# Qwiic_Scale.net
KiCad netlist of a schematic drawn in EAGLE
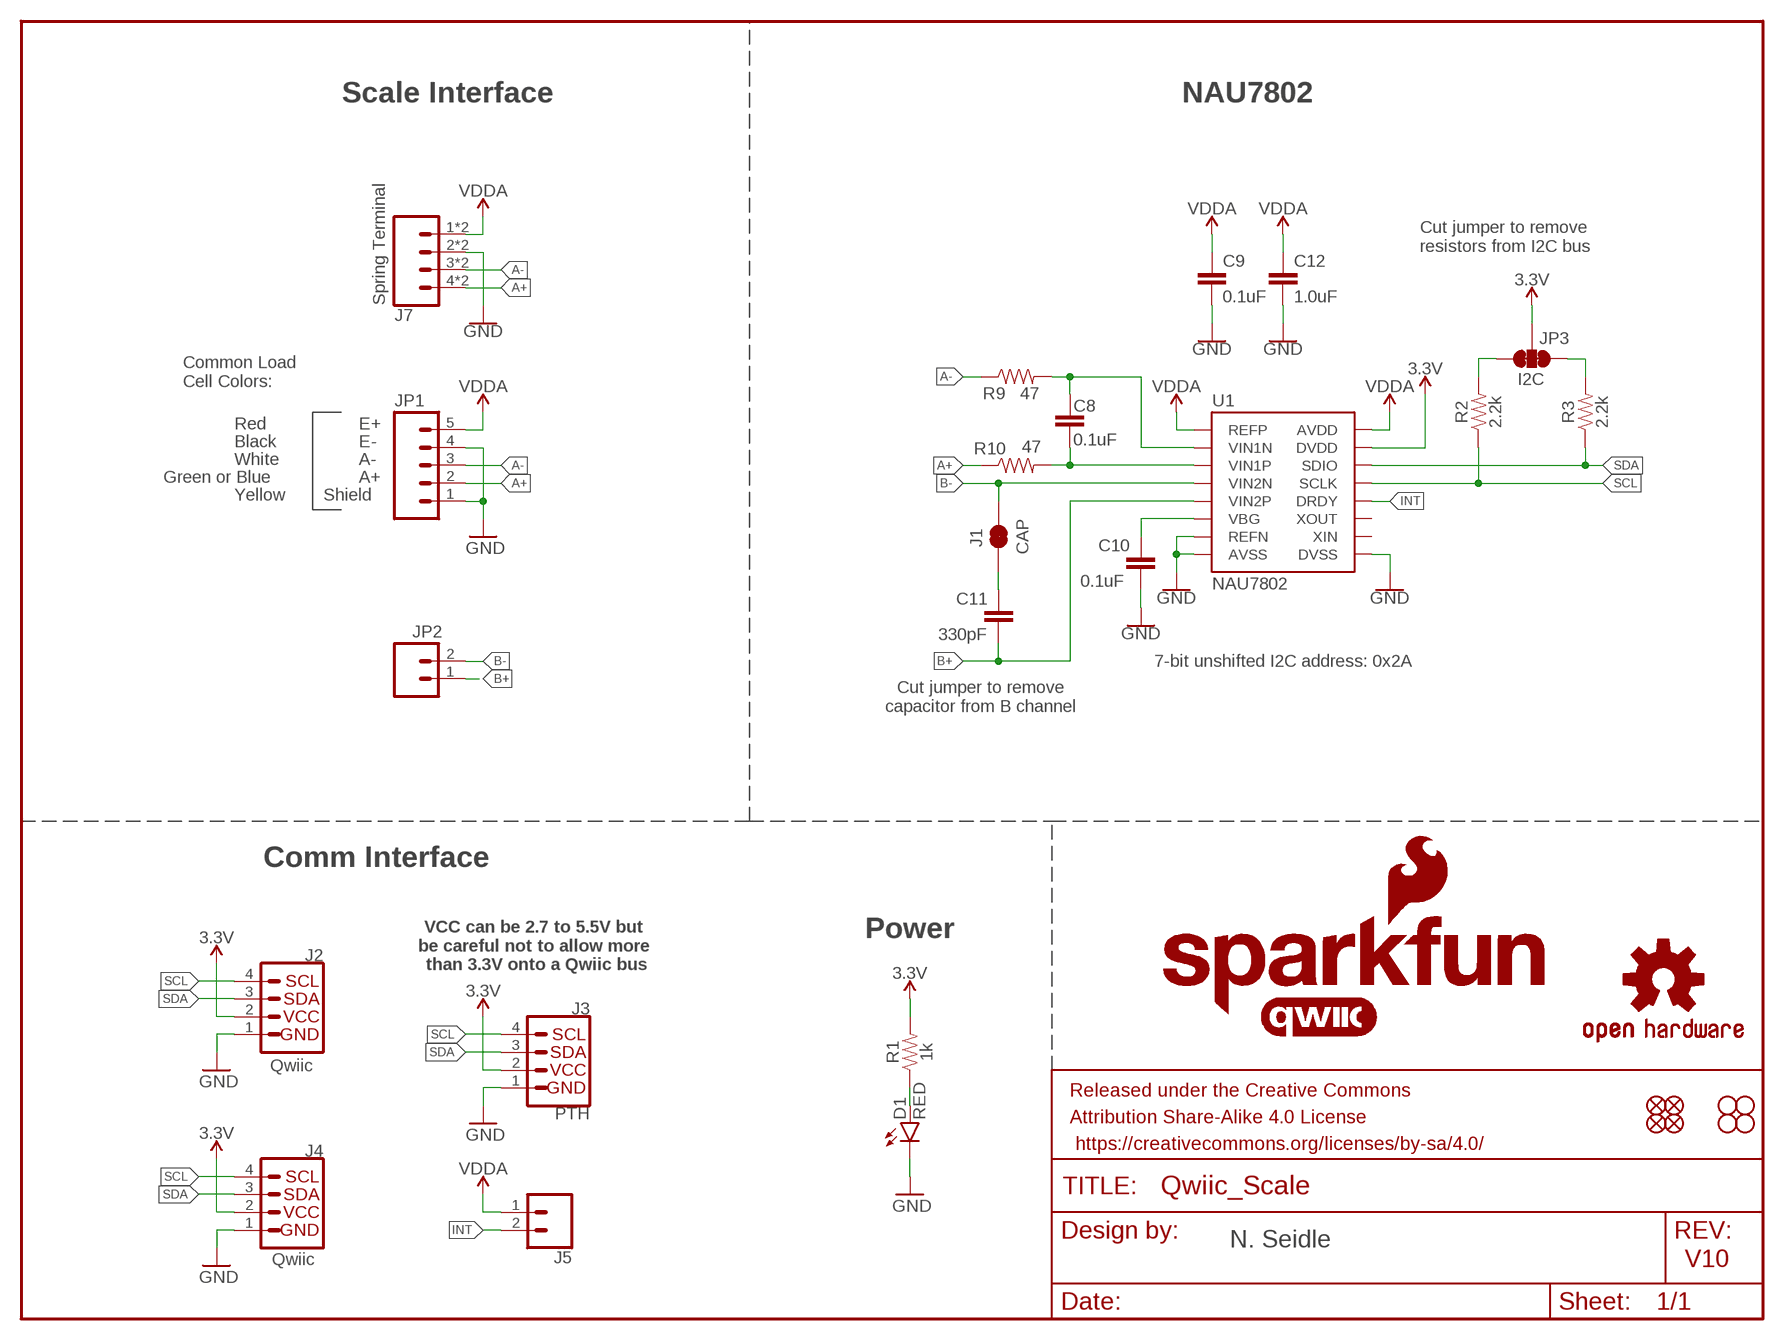
[diagram p0: schematic, sheet 1]

(export (version "E")
  (design (tool "Eeschema 10.0.6"))
  (components
    (comp (ref "C8")
      (value "0.1uF")
      (footprint "eagle-import:0603")
      (libsource (lib "eagle-import") (part "0.1UF-0603-25V-(+80/-20%)"))
    )
    (comp (ref "C9")
      (value "0.1uF")
      (footprint "eagle-import:0603")
      (libsource (lib "eagle-import") (part "0.1UF-0603-25V-(+80/-20%)"))
    )
    (comp (ref "C10")
      (value "0.1uF")
      (footprint "eagle-import:0603")
      (libsource (lib "eagle-import") (part "0.1UF-0603-25V-(+80/-20%)"))
    )
    (comp (ref "C11")
      (value "330pF")
      (footprint "eagle-import:0603")
      (libsource (lib "eagle-import") (part "330PF-0603-50V-5%"))
    )
    (comp (ref "C12")
      (value "1.0uF")
      (footprint "eagle-import:0603")
      (libsource (lib "eagle-import") (part "1.0UF-0603-16V-10%"))
    )
    (comp (ref "D1")
      (value "RED")
      (footprint "eagle-import:LED-0603")
      (libsource (lib "eagle-import") (part "LED-RED0603"))
    )
    (comp (ref "FRAME1")
      (value "FRAME-LETTER")
      (footprint "eagle-import:CREATIVE_COMMONS")
      (libsource (lib "eagle-import") (part "FRAME-LETTER"))
    )
    (comp (ref "J1")
      (value "CAP")
      (footprint "eagle-import:SMT-JUMPER_2_NC_TRACE_SILK")
      (libsource (lib "eagle-import") (part "JUMPER-SMT_2_NC_TRACE_SILK"))
    )
    (comp (ref "J2")
      (value "Qwiic")
      (footprint "eagle-import:JST04_1MM_RA")
      (libsource (lib "eagle-import") (part "I2C_STANDARDQWIIC"))
    )
    (comp (ref "J3")
      (value "PTH")
      (footprint "eagle-import:1X04_NO_SILK")
      (libsource (lib "eagle-import") (part "I2C_STANDARD_NO_SILK"))
    )
    (comp (ref "J4")
      (value "Qwiic")
      (footprint "eagle-import:JST04_1MM_RA")
      (libsource (lib "eagle-import") (part "I2C_STANDARDQWIIC"))
    )
    (comp (ref "J5")
      (value "CONN_021X02_NO_SILK")
      (footprint "eagle-import:1X02_NO_SILK")
      (libsource (lib "eagle-import") (part "CONN_021X02_NO_SILK"))
    )
    (comp (ref "J7")
      (value "Spring Terminal")
      (footprint "eagle-import:1X04_SPRING_TERMINAL")
      (libsource (lib "eagle-import") (part "CONN_04SPRING"))
    )
    (comp (ref "JP1")
      (value "CONN_05NO_SILK")
      (footprint "eagle-import:1X05_NO_SILK")
      (libsource (lib "eagle-import") (part "CONN_05NO_SILK"))
    )
    (comp (ref "JP2")
      (value "CONN_021X02_NO_SILK")
      (footprint "eagle-import:1X02_NO_SILK")
      (libsource (lib "eagle-import") (part "CONN_021X02_NO_SILK"))
    )
    (comp (ref "JP3")
      (value "I2C")
      (footprint "eagle-import:SMT-JUMPER_3_2-NC_TRACE_SILK")
      (libsource (lib "eagle-import") (part "JUMPER-SMT_3_2-NC_TRACE_SILK"))
    )
    (comp (ref "JP21")
      (value "FIDUCIALUFIDUCIAL")
      (footprint "eagle-import:MICRO-FIDUCIAL")
      (libsource (lib "eagle-import") (part "FIDUCIALUFIDUCIAL"))
    )
    (comp (ref "JP31")
      (value "STAND-OFF")
      (footprint "eagle-import:STAND-OFF")
      (libsource (lib "eagle-import") (part "STAND-OFF"))
    )
    (comp (ref "JP41")
      (value "STAND-OFF")
      (footprint "eagle-import:STAND-OFF")
      (libsource (lib "eagle-import") (part "STAND-OFF"))
    )
    (comp (ref "JP61")
      (value "FIDUCIALUFIDUCIAL")
      (footprint "eagle-import:MICRO-FIDUCIAL")
      (libsource (lib "eagle-import") (part "FIDUCIALUFIDUCIAL"))
    )
    (comp (ref "JP71")
      (value "FIDUCIALUFIDUCIAL")
      (footprint "eagle-import:MICRO-FIDUCIAL")
      (libsource (lib "eagle-import") (part "FIDUCIALUFIDUCIAL"))
    )
    (comp (ref "JP81")
      (value "FIDUCIALUFIDUCIAL")
      (footprint "eagle-import:MICRO-FIDUCIAL")
      (libsource (lib "eagle-import") (part "FIDUCIALUFIDUCIAL"))
    )
    (comp (ref "JP91")
      (value "STAND-OFF")
      (footprint "eagle-import:STAND-OFF")
      (libsource (lib "eagle-import") (part "STAND-OFF"))
    )
    (comp (ref "JP101")
      (value "STAND-OFF")
      (footprint "eagle-import:STAND-OFF")
      (libsource (lib "eagle-import") (part "STAND-OFF"))
    )
    (comp (ref "LOGO1")
      (value "OSHW-LOGOMINI")
      (footprint "eagle-import:OSHW-LOGO-MINI")
      (libsource (lib "eagle-import") (part "OSHW-LOGOMINI"))
    )
    (comp (ref "LOGO2")
      (value "SFE_LOGO_NAME_FLAME.1_INCH")
      (footprint "eagle-import:SFE_LOGO_NAME_FLAME_.1")
      (libsource (lib "eagle-import") (part "SFE_LOGO_NAME_FLAME.1_INCH"))
    )
    (comp (ref "R1")
      (value "1k")
      (footprint "eagle-import:0603")
      (libsource (lib "eagle-import") (part "1KOHM-0603-1/10W-1%"))
    )
    (comp (ref "R2")
      (value "2.2k")
      (footprint "eagle-import:0603")
      (libsource (lib "eagle-import") (part "2.2KOHM-0603-1/10W-1%"))
    )
    (comp (ref "R3")
      (value "2.2k")
      (footprint "eagle-import:0603")
      (libsource (lib "eagle-import") (part "2.2KOHM-0603-1/10W-1%"))
    )
    (comp (ref "R9")
      (value "47")
      (footprint "eagle-import:0603")
      (libsource (lib "eagle-import") (part "47OHM-0603-1/10W-1%"))
    )
    (comp (ref "R10")
      (value "47")
      (footprint "eagle-import:0603")
      (libsource (lib "eagle-import") (part "47OHM-0603-1/10W-1%"))
    )
    (comp (ref "U$16")
      (value "QWIIC_LOGO_7MM")
      (footprint "eagle-import:QWIIC_7MM")
      (libsource (lib "eagle-import") (part "QWIIC_LOGO_7MM"))
    )
    (comp (ref "U1")
      (value "NAU7802")
      (footprint "eagle-import:SO16")
      (libsource (lib "eagle-import") (part "NAU7802SOIC"))
    )
  )
  (nets
    (net (code "1") (name "3.3V") (class "Default")
      (node (ref "J2") (pin "2") (pinfunction "2_2") (pintype "power_in"))
      (node (ref "J3") (pin "2") (pinfunction "2_2") (pintype "power_in"))
      (node (ref "J4") (pin "2") (pinfunction "2_2") (pintype "power_in"))
      (node (ref "JP3") (pin "2") (pinfunction "2_2") (pintype "passive"))
      (node (ref "R1") (pin "2") (pinfunction "2_2") (pintype "passive"))
      (node (ref "U1") (pin "15") (pinfunction "DVDD_15") (pintype "bidirectional"))
    )
    (net (code "2") (name "A+") (class "Default")
      (node (ref "J7") (pin "4") (pinfunction "4_4") (pintype "passive"))
      (node (ref "J7") (pin "8") (pinfunction "4_8") (pintype "passive"))
      (node (ref "JP1") (pin "2") (pinfunction "2_2") (pintype "passive"))
      (node (ref "R10") (pin "1") (pinfunction "1_1") (pintype "passive"))
    )
    (net (code "3") (name "A-") (class "Default")
      (node (ref "J7") (pin "3") (pinfunction "3_3") (pintype "passive"))
      (node (ref "J7") (pin "7") (pinfunction "3_7") (pintype "passive"))
      (node (ref "JP1") (pin "3") (pinfunction "3_3") (pintype "passive"))
      (node (ref "R9") (pin "1") (pinfunction "1_1") (pintype "passive"))
    )
    (net (code "4") (name "B+") (class "Default")
      (node (ref "C11") (pin "2") (pinfunction "2_2") (pintype "passive"))
      (node (ref "JP2") (pin "1") (pinfunction "1_1") (pintype "passive"))
      (node (ref "U1") (pin "5") (pinfunction "VIN2P_5") (pintype "bidirectional"))
    )
    (net (code "5") (name "B-") (class "Default")
      (node (ref "J1") (pin "2") (pinfunction "2_2") (pintype "passive"))
      (node (ref "JP2") (pin "2") (pinfunction "2_2") (pintype "passive"))
      (node (ref "U1") (pin "4") (pinfunction "VIN2N_4") (pintype "bidirectional"))
    )
    (net (code "6") (name "GND") (class "Default")
      (node (ref "C10") (pin "2") (pinfunction "2_2") (pintype "passive"))
      (node (ref "C12") (pin "2") (pinfunction "2_2") (pintype "passive"))
      (node (ref "C9") (pin "2") (pinfunction "2_2") (pintype "passive"))
      (node (ref "D1") (pin "C") (pinfunction "C_C") (pintype "passive"))
      (node (ref "J2") (pin "1") (pinfunction "1_1") (pintype "power_in"))
      (node (ref "J3") (pin "1") (pinfunction "1_1") (pintype "power_in"))
      (node (ref "J4") (pin "1") (pinfunction "1_1") (pintype "power_in"))
      (node (ref "J7") (pin "2") (pinfunction "2_2") (pintype "passive"))
      (node (ref "J7") (pin "6") (pinfunction "2_6") (pintype "passive"))
      (node (ref "JP1") (pin "1") (pinfunction "1_1") (pintype "passive"))
      (node (ref "JP1") (pin "4") (pinfunction "4_4") (pintype "passive"))
      (node (ref "U1") (pin "7") (pinfunction "REFN_7") (pintype "bidirectional"))
      (node (ref "U1") (pin "8") (pinfunction "AVSS_8") (pintype "bidirectional"))
      (node (ref "U1") (pin "9") (pinfunction "DVSS_9") (pintype "bidirectional"))
    )
    (net (code "7") (name "INT") (class "Default")
      (node (ref "J5") (pin "2") (pinfunction "2_2") (pintype "passive"))
      (node (ref "U1") (pin "12") (pinfunction "DRDY_12") (pintype "bidirectional"))
    )
    (net (code "8") (name "Net-(C11-Pad1)") (class "Default")
      (node (ref "C11") (pin "1") (pinfunction "1_1") (pintype "passive"))
      (node (ref "J1") (pin "1") (pinfunction "1_1") (pintype "passive"))
    )
    (net (code "9") (name "Net-(D1-PadA)") (class "Default")
      (node (ref "D1") (pin "A") (pinfunction "A_A") (pintype "passive"))
      (node (ref "R1") (pin "1") (pinfunction "1_1") (pintype "passive"))
    )
    (net (code "10") (name "Net-(JP3-Pad1)") (class "Default")
      (node (ref "JP3") (pin "1") (pinfunction "1_1") (pintype "passive"))
      (node (ref "R3") (pin "2") (pinfunction "2_2") (pintype "passive"))
    )
    (net (code "11") (name "Net-(JP3-Pad3)") (class "Default")
      (node (ref "JP3") (pin "3") (pinfunction "3_3") (pintype "passive"))
      (node (ref "R2") (pin "2") (pinfunction "2_2") (pintype "passive"))
    )
    (net (code "12") (name "Net-(U1-VBG)") (class "Default")
      (node (ref "C10") (pin "1") (pinfunction "1_1") (pintype "passive"))
      (node (ref "U1") (pin "6") (pinfunction "VBG_6") (pintype "bidirectional"))
    )
    (net (code "13") (name "Net-(U1-VIN1N)") (class "Default")
      (node (ref "C8") (pin "1") (pinfunction "1_1") (pintype "passive"))
      (node (ref "R9") (pin "2") (pinfunction "2_2") (pintype "passive"))
      (node (ref "U1") (pin "2") (pinfunction "VIN1N_2") (pintype "bidirectional"))
    )
    (net (code "14") (name "Net-(U1-VIN1P)") (class "Default")
      (node (ref "C8") (pin "2") (pinfunction "2_2") (pintype "passive"))
      (node (ref "R10") (pin "2") (pinfunction "2_2") (pintype "passive"))
      (node (ref "U1") (pin "3") (pinfunction "VIN1P_3") (pintype "bidirectional"))
    )
    (net (code "15") (name "SCL") (class "Default")
      (node (ref "J2") (pin "4") (pinfunction "4_4") (pintype "passive"))
      (node (ref "J3") (pin "4") (pinfunction "4_4") (pintype "passive"))
      (node (ref "J4") (pin "4") (pinfunction "4_4") (pintype "passive"))
      (node (ref "R2") (pin "1") (pinfunction "1_1") (pintype "passive"))
      (node (ref "U1") (pin "13") (pinfunction "SCLK_13") (pintype "bidirectional"))
    )
    (net (code "16") (name "SDA") (class "Default")
      (node (ref "J2") (pin "3") (pinfunction "3_3") (pintype "passive"))
      (node (ref "J3") (pin "3") (pinfunction "3_3") (pintype "passive"))
      (node (ref "J4") (pin "3") (pinfunction "3_3") (pintype "passive"))
      (node (ref "R3") (pin "1") (pinfunction "1_1") (pintype "passive"))
      (node (ref "U1") (pin "14") (pinfunction "SDIO_14") (pintype "bidirectional"))
    )
    (net (code "17") (name "VDDA") (class "Default")
      (node (ref "C12") (pin "1") (pinfunction "1_1") (pintype "passive"))
      (node (ref "C9") (pin "1") (pinfunction "1_1") (pintype "passive"))
      (node (ref "J5") (pin "1") (pinfunction "1_1") (pintype "passive"))
      (node (ref "J7") (pin "1") (pinfunction "1_1") (pintype "passive"))
      (node (ref "J7") (pin "5") (pinfunction "1_5") (pintype "passive"))
      (node (ref "JP1") (pin "5") (pinfunction "5_5") (pintype "passive"))
      (node (ref "U1") (pin "1") (pinfunction "REFP_1") (pintype "bidirectional"))
      (node (ref "U1") (pin "16") (pinfunction "AVDD_16") (pintype "bidirectional"))
    )
    (net (code "18") (name "unconnected-(U1-XIN-Pad10)") (class "Default")
      (node (ref "U1") (pin "10") (pinfunction "XIN_10") (pintype "bidirectional"))
    )
    (net (code "19") (name "unconnected-(U1-XOUT-Pad11)") (class "Default")
      (node (ref "U1") (pin "11") (pinfunction "XOUT_11") (pintype "bidirectional"))
    )
  )
)
